# Microcontroller_board_Photodiode_plate.net
KiCad netlist of a schematic drawn in EasyEDA
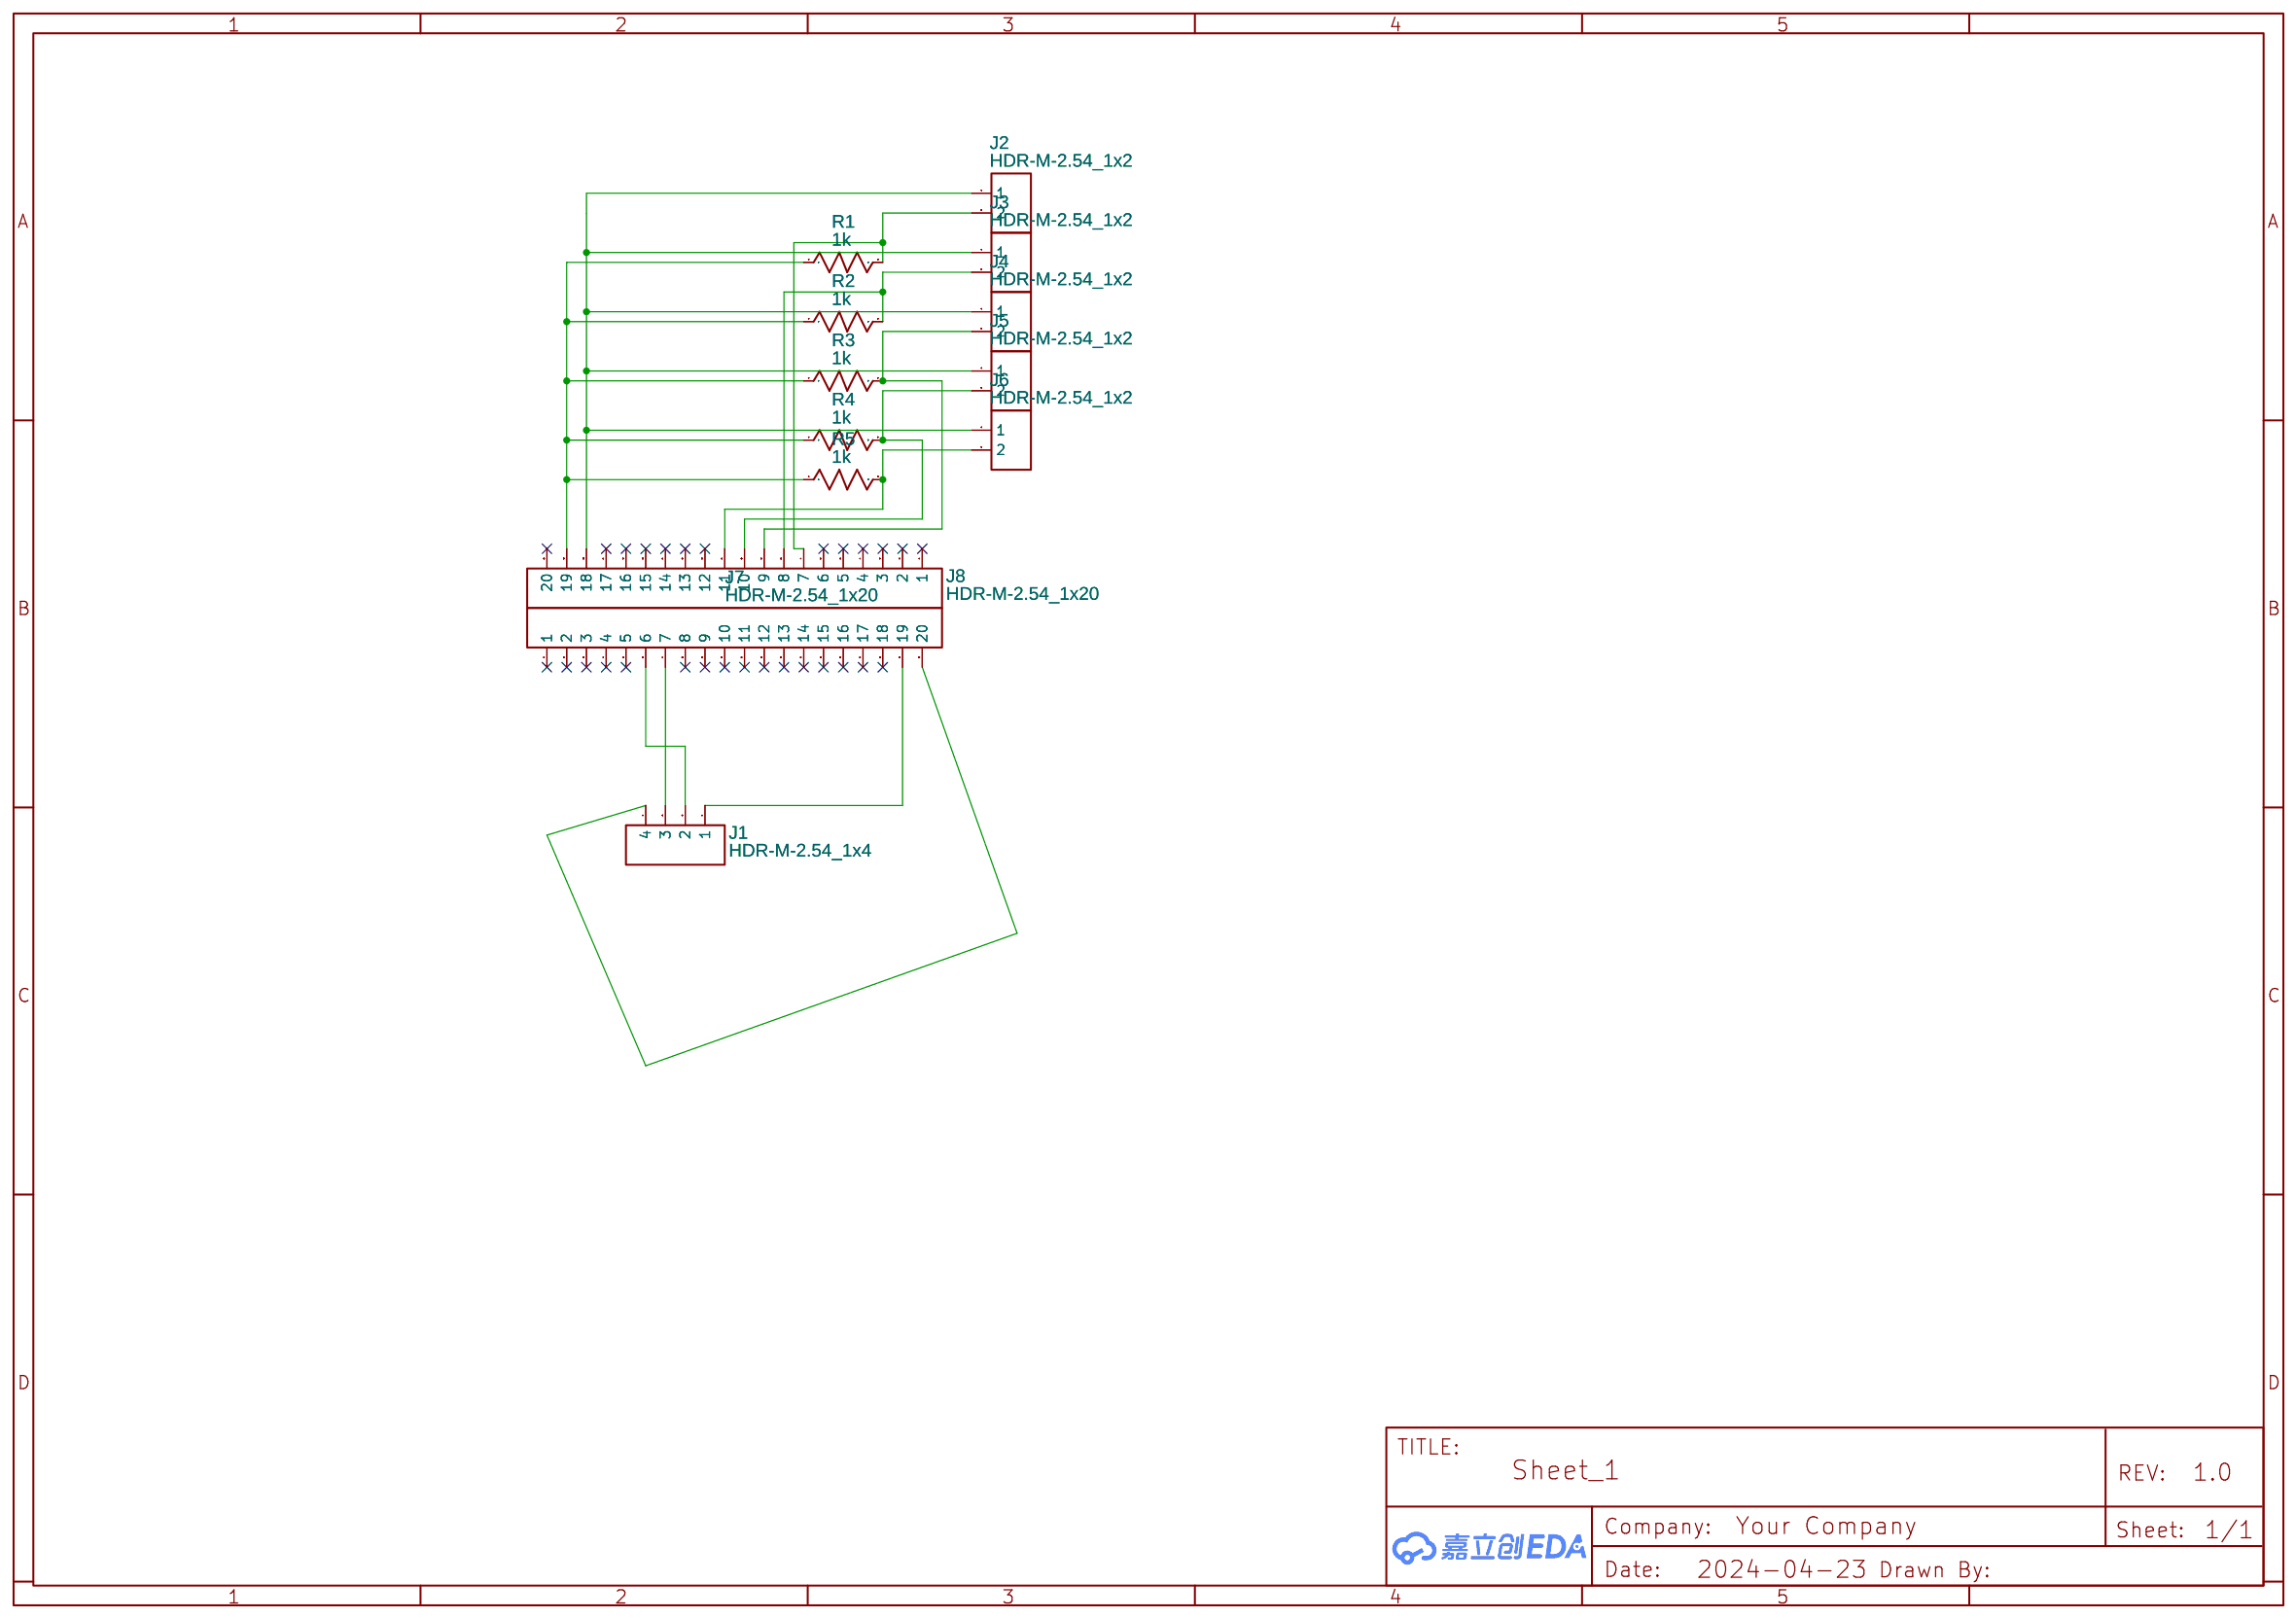
[diagram p0: schematic sheet]

(export (version "E")
  (design (tool "Eeschema 10.0.6"))
  (components
    (comp (ref "J1")
      (value "HDR-M-2.54_1x4")
      (fields (field (name "BOM_Supplier Part") "C124378"))
      (libsource (lib "") (part "HDR-M-2.54_1x4"))
    )
    (comp (ref "J2")
      (value "HDR-M-2.54_1x2")
      (fields (field (name "BOM_Supplier Part") "C124375"))
      (libsource (lib "") (part "HDR-M-2.54_1x2"))
    )
    (comp (ref "J3")
      (value "HDR-M-2.54_1x2")
      (fields (field (name "BOM_Supplier Part") "C124375"))
      (libsource (lib "") (part "HDR-M-2.54_1x2"))
    )
    (comp (ref "J4")
      (value "HDR-M-2.54_1x2")
      (fields (field (name "BOM_Supplier Part") "C124375"))
      (libsource (lib "") (part "HDR-M-2.54_1x2"))
    )
    (comp (ref "J5")
      (value "HDR-M-2.54_1x2")
      (fields (field (name "BOM_Supplier Part") "C124375"))
      (libsource (lib "") (part "HDR-M-2.54_1x2"))
    )
    (comp (ref "J6")
      (value "HDR-M-2.54_1x2")
      (fields (field (name "BOM_Supplier Part") "C124375"))
      (libsource (lib "") (part "HDR-M-2.54_1x2"))
    )
    (comp (ref "J7")
      (value "HDR-M-2.54_1x20")
      (fields (field (name "BOM_Supplier Part") "C50981"))
      (libsource (lib "") (part "HDR-M-2.54_1x20_1"))
    )
    (comp (ref "J8")
      (value "HDR-M-2.54_1x20")
      (fields (field (name "BOM_Supplier Part") "C50981"))
      (libsource (lib "") (part "HDR-M-2.54_1x20"))
    )
    (comp (ref "R1") (value "1k") (libsource (lib "") (part "R_AXIAL-0.3_US")))
    (comp (ref "R2") (value "1k") (libsource (lib "") (part "R_AXIAL-0.3_US")))
    (comp (ref "R3") (value "1k") (libsource (lib "") (part "R_AXIAL-0.3_US")))
    (comp (ref "R4") (value "1k") (libsource (lib "") (part "R_AXIAL-0.3_US")))
    (comp (ref "R5") (value "1k") (libsource (lib "") (part "R_AXIAL-0.3_US")))
  )
  (nets
    (net (code "1") (name "Net-(J1-Pad1)") (class "Default")
      (node (ref "J1") (pin "1") (pinfunction "1_1") (pintype "unspecified"))
      (node (ref "J7") (pin "19") (pinfunction "19_19") (pintype "unspecified"))
    )
    (net (code "2") (name "Net-(J1-Pad2)") (class "Default")
      (node (ref "J1") (pin "2") (pinfunction "2_2") (pintype "unspecified"))
      (node (ref "J7") (pin "6") (pinfunction "6_6") (pintype "unspecified"))
    )
    (net (code "3") (name "Net-(J1-Pad3)") (class "Default")
      (node (ref "J1") (pin "3") (pinfunction "3_3") (pintype "unspecified"))
      (node (ref "J7") (pin "7") (pinfunction "7_7") (pintype "unspecified"))
    )
    (net (code "4") (name "Net-(J1-Pad4)") (class "Default")
      (node (ref "J1") (pin "4") (pinfunction "4_4") (pintype "unspecified"))
      (node (ref "J7") (pin "20") (pinfunction "20_20") (pintype "unspecified"))
    )
    (net (code "5") (name "Net-(J2-Pad1)") (class "Default")
      (node (ref "J2") (pin "1") (pinfunction "1_1") (pintype "unspecified"))
      (node (ref "J3") (pin "1") (pinfunction "1_1") (pintype "unspecified"))
      (node (ref "J4") (pin "1") (pinfunction "1_1") (pintype "unspecified"))
      (node (ref "J5") (pin "1") (pinfunction "1_1") (pintype "unspecified"))
      (node (ref "J6") (pin "1") (pinfunction "1_1") (pintype "unspecified"))
      (node (ref "J8") (pin "18") (pinfunction "18_18") (pintype "unspecified"))
    )
    (net (code "6") (name "Net-(J2-Pad2)") (class "Default")
      (node (ref "J2") (pin "2") (pinfunction "2_2") (pintype "unspecified"))
      (node (ref "J8") (pin "7") (pinfunction "7_7") (pintype "unspecified"))
      (node (ref "R1") (pin "2") (pinfunction "2_2") (pintype "unspecified"))
    )
    (net (code "7") (name "Net-(J3-Pad2)") (class "Default")
      (node (ref "J3") (pin "2") (pinfunction "2_2") (pintype "unspecified"))
      (node (ref "J8") (pin "8") (pinfunction "8_8") (pintype "unspecified"))
      (node (ref "R2") (pin "2") (pinfunction "2_2") (pintype "unspecified"))
    )
    (net (code "8") (name "Net-(J4-Pad2)") (class "Default")
      (node (ref "J4") (pin "2") (pinfunction "2_2") (pintype "unspecified"))
      (node (ref "J8") (pin "9") (pinfunction "9_9") (pintype "unspecified"))
      (node (ref "R3") (pin "2") (pinfunction "2_2") (pintype "unspecified"))
    )
    (net (code "9") (name "Net-(J5-Pad2)") (class "Default")
      (node (ref "J5") (pin "2") (pinfunction "2_2") (pintype "unspecified"))
      (node (ref "J8") (pin "10") (pinfunction "10_10") (pintype "unspecified"))
      (node (ref "R4") (pin "2") (pinfunction "2_2") (pintype "unspecified"))
    )
    (net (code "10") (name "Net-(J6-Pad2)") (class "Default")
      (node (ref "J6") (pin "2") (pinfunction "2_2") (pintype "unspecified"))
      (node (ref "J8") (pin "11") (pinfunction "11_11") (pintype "unspecified"))
      (node (ref "R5") (pin "2") (pinfunction "2_2") (pintype "unspecified"))
    )
    (net (code "11") (name "Net-(J8-Pad19)") (class "Default")
      (node (ref "J8") (pin "19") (pinfunction "19_19") (pintype "unspecified"))
      (node (ref "R1") (pin "1") (pinfunction "1_1") (pintype "unspecified"))
      (node (ref "R2") (pin "1") (pinfunction "1_1") (pintype "unspecified"))
      (node (ref "R3") (pin "1") (pinfunction "1_1") (pintype "unspecified"))
      (node (ref "R4") (pin "1") (pinfunction "1_1") (pintype "unspecified"))
      (node (ref "R5") (pin "1") (pinfunction "1_1") (pintype "unspecified"))
    )
    (net (code "12") (name "unconnected-(J7-Pad1)") (class "Default")
      (node (ref "J7") (pin "1") (pinfunction "1_1") (pintype "unspecified+no_connect"))
    )
    (net (code "13") (name "unconnected-(J7-Pad2)") (class "Default")
      (node (ref "J7") (pin "2") (pinfunction "2_2") (pintype "unspecified+no_connect"))
    )
    (net (code "14") (name "unconnected-(J7-Pad3)") (class "Default")
      (node (ref "J7") (pin "3") (pinfunction "3_3") (pintype "unspecified+no_connect"))
    )
    (net (code "15") (name "unconnected-(J7-Pad4)") (class "Default")
      (node (ref "J7") (pin "4") (pinfunction "4_4") (pintype "unspecified+no_connect"))
    )
    (net (code "16") (name "unconnected-(J7-Pad5)") (class "Default")
      (node (ref "J7") (pin "5") (pinfunction "5_5") (pintype "unspecified+no_connect"))
    )
    (net (code "17") (name "unconnected-(J7-Pad8)") (class "Default")
      (node (ref "J7") (pin "8") (pinfunction "8_8") (pintype "unspecified+no_connect"))
    )
    (net (code "18") (name "unconnected-(J7-Pad9)") (class "Default")
      (node (ref "J7") (pin "9") (pinfunction "9_9") (pintype "unspecified+no_connect"))
    )
    (net (code "19") (name "unconnected-(J7-Pad10)") (class "Default")
      (node (ref "J7") (pin "10") (pinfunction "10_10") (pintype "unspecified+no_connect"))
    )
    (net (code "20") (name "unconnected-(J7-Pad11)") (class "Default")
      (node (ref "J7") (pin "11") (pinfunction "11_11") (pintype "unspecified+no_connect"))
    )
    (net (code "21") (name "unconnected-(J7-Pad12)") (class "Default")
      (node (ref "J7") (pin "12") (pinfunction "12_12") (pintype "unspecified+no_connect"))
    )
    (net (code "22") (name "unconnected-(J7-Pad13)") (class "Default")
      (node (ref "J7") (pin "13") (pinfunction "13_13") (pintype "unspecified+no_connect"))
    )
    (net (code "23") (name "unconnected-(J7-Pad14)") (class "Default")
      (node (ref "J7") (pin "14") (pinfunction "14_14") (pintype "unspecified+no_connect"))
    )
    (net (code "24") (name "unconnected-(J7-Pad15)") (class "Default")
      (node (ref "J7") (pin "15") (pinfunction "15_15") (pintype "unspecified+no_connect"))
    )
    (net (code "25") (name "unconnected-(J7-Pad16)") (class "Default")
      (node (ref "J7") (pin "16") (pinfunction "16_16") (pintype "unspecified+no_connect"))
    )
    (net (code "26") (name "unconnected-(J7-Pad17)") (class "Default")
      (node (ref "J7") (pin "17") (pinfunction "17_17") (pintype "unspecified+no_connect"))
    )
    (net (code "27") (name "unconnected-(J7-Pad18)") (class "Default")
      (node (ref "J7") (pin "18") (pinfunction "18_18") (pintype "unspecified+no_connect"))
    )
    (net (code "28") (name "unconnected-(J8-Pad1)") (class "Default")
      (node (ref "J8") (pin "1") (pinfunction "1_1") (pintype "unspecified+no_connect"))
    )
    (net (code "29") (name "unconnected-(J8-Pad2)") (class "Default")
      (node (ref "J8") (pin "2") (pinfunction "2_2") (pintype "unspecified+no_connect"))
    )
    (net (code "30") (name "unconnected-(J8-Pad3)") (class "Default")
      (node (ref "J8") (pin "3") (pinfunction "3_3") (pintype "unspecified+no_connect"))
    )
    (net (code "31") (name "unconnected-(J8-Pad4)") (class "Default")
      (node (ref "J8") (pin "4") (pinfunction "4_4") (pintype "unspecified+no_connect"))
    )
    (net (code "32") (name "unconnected-(J8-Pad5)") (class "Default")
      (node (ref "J8") (pin "5") (pinfunction "5_5") (pintype "unspecified+no_connect"))
    )
    (net (code "33") (name "unconnected-(J8-Pad6)") (class "Default")
      (node (ref "J8") (pin "6") (pinfunction "6_6") (pintype "unspecified+no_connect"))
    )
    (net (code "34") (name "unconnected-(J8-Pad12)") (class "Default")
      (node (ref "J8") (pin "12") (pinfunction "12_12") (pintype "unspecified+no_connect"))
    )
    (net (code "35") (name "unconnected-(J8-Pad13)") (class "Default")
      (node (ref "J8") (pin "13") (pinfunction "13_13") (pintype "unspecified+no_connect"))
    )
    (net (code "36") (name "unconnected-(J8-Pad14)") (class "Default")
      (node (ref "J8") (pin "14") (pinfunction "14_14") (pintype "unspecified+no_connect"))
    )
    (net (code "37") (name "unconnected-(J8-Pad15)") (class "Default")
      (node (ref "J8") (pin "15") (pinfunction "15_15") (pintype "unspecified+no_connect"))
    )
    (net (code "38") (name "unconnected-(J8-Pad16)") (class "Default")
      (node (ref "J8") (pin "16") (pinfunction "16_16") (pintype "unspecified+no_connect"))
    )
    (net (code "39") (name "unconnected-(J8-Pad17)") (class "Default")
      (node (ref "J8") (pin "17") (pinfunction "17_17") (pintype "unspecified+no_connect"))
    )
    (net (code "40") (name "unconnected-(J8-Pad20)") (class "Default")
      (node (ref "J8") (pin "20") (pinfunction "20_20") (pintype "unspecified+no_connect"))
    )
  )
)
